# FEU-102-1_part5.net
KiCad netlist of a schematic drawn in Altium Designer
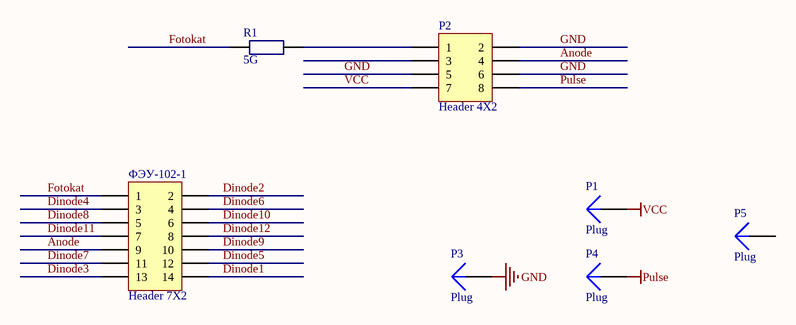
[diagram p0: FEU-102-1_part5.SchDoc]

(export (version "E")
  (design (tool "Eeschema 10.0.6"))
  (components
    (comp (ref "P1")
      (value "Plug")
      (footprint "PIN1")
      (fields (field (name "PUBLISHER") "Altium Limited"))
      (libsource (lib "Miscellaneous Connectors") (part "Plug"))
    )
    (comp (ref "P2")
      (value "Header 4X2")
      (footprint "HDR2X4")
      (description "Header, 4-Pin, Dual row")
      (fields (field (name "PUBLISHER") "Altium Limited"))
      (libsource (lib "Miscellaneous Connectors") (part "Header 4X2"))
    )
    (comp (ref "P3")
      (value "Plug")
      (footprint "PIN1")
      (fields (field (name "PUBLISHER") "Altium Limited"))
      (libsource (lib "Miscellaneous Connectors") (part "Plug"))
    )
    (comp (ref "P4")
      (value "Plug")
      (footprint "PIN1")
      (fields (field (name "PUBLISHER") "Altium Limited"))
      (libsource (lib "Miscellaneous Connectors") (part "Plug"))
    )
    (comp (ref "P5")
      (value "Plug")
      (footprint "PIN1")
      (fields (field (name "PUBLISHER") "Altium Limited"))
      (libsource (lib "Miscellaneous Connectors") (part "Plug"))
    )
    (comp (ref "R1")
      (value "5G")
      (footprint "HVF2512T5007FE")
      (libsource (lib "Микрон-3") (part "Resistor 0805"))
    )
    (comp (ref "ФЭУ-102-1")
      (value "Header 7X2")
      (footprint "ФЭУ-102")
      (description "Header, 7-Pin, Dual row")
      (fields (field (name "PUBLISHER") "Altium Limited"))
      (libsource (lib "Miscellaneous Connectors") (part "Header 7X2"))
    )
  )
  (nets
    (net (code "1") (name "/Anode") (class "Default")
      (node (ref "P2") (pin "4") (pinfunction "4_4") (pintype "passive"))
      (node (ref "ФЭУ-102-1") (pin "9") (pinfunction "9_9") (pintype "passive"))
    )
    (net (code "2") (name "/Dinode1") (class "Default")
      (node (ref "ФЭУ-102-1") (pin "14") (pinfunction "14_14") (pintype "passive"))
    )
    (net (code "3") (name "/Dinode2") (class "Default")
      (node (ref "ФЭУ-102-1") (pin "2") (pinfunction "2_2") (pintype "passive"))
    )
    (net (code "4") (name "/Dinode3") (class "Default")
      (node (ref "ФЭУ-102-1") (pin "13") (pinfunction "13_13") (pintype "passive"))
    )
    (net (code "5") (name "/Dinode4") (class "Default")
      (node (ref "ФЭУ-102-1") (pin "3") (pinfunction "3_3") (pintype "passive"))
    )
    (net (code "6") (name "/Dinode5") (class "Default")
      (node (ref "ФЭУ-102-1") (pin "12") (pinfunction "12_12") (pintype "passive"))
    )
    (net (code "7") (name "/Dinode6") (class "Default")
      (node (ref "ФЭУ-102-1") (pin "4") (pinfunction "4_4") (pintype "passive"))
    )
    (net (code "8") (name "/Dinode7") (class "Default")
      (node (ref "ФЭУ-102-1") (pin "11") (pinfunction "11_11") (pintype "passive"))
    )
    (net (code "9") (name "/Dinode8") (class "Default")
      (node (ref "ФЭУ-102-1") (pin "5") (pinfunction "5_5") (pintype "passive"))
    )
    (net (code "10") (name "/Dinode9") (class "Default")
      (node (ref "ФЭУ-102-1") (pin "10") (pinfunction "10_10") (pintype "passive"))
    )
    (net (code "11") (name "/Dinode10") (class "Default")
      (node (ref "ФЭУ-102-1") (pin "6") (pinfunction "6_6") (pintype "passive"))
    )
    (net (code "12") (name "/Dinode11") (class "Default")
      (node (ref "ФЭУ-102-1") (pin "7") (pinfunction "7_7") (pintype "passive"))
    )
    (net (code "13") (name "/Dinode12") (class "Default")
      (node (ref "ФЭУ-102-1") (pin "8") (pinfunction "8_8") (pintype "passive"))
    )
    (net (code "14") (name "/Fotokat") (class "Default")
      (node (ref "R1") (pin "1") (pinfunction "A_1") (pintype "passive"))
      (node (ref "ФЭУ-102-1") (pin "1") (pinfunction "1_1") (pintype "passive"))
    )
    (net (code "15") (name "GND") (class "Default")
      (node (ref "P2") (pin "2") (pinfunction "2_2") (pintype "passive"))
      (node (ref "P2") (pin "5") (pinfunction "5_5") (pintype "passive"))
      (node (ref "P2") (pin "6") (pinfunction "6_6") (pintype "passive"))
      (node (ref "P3") (pin "1") (pinfunction "1_1") (pintype "passive"))
    )
    (net (code "16") (name "Net-(P2-Pad1)") (class "Default")
      (node (ref "P2") (pin "1") (pinfunction "1_1") (pintype "passive"))
      (node (ref "R1") (pin "2") (pinfunction "2_2") (pintype "passive"))
    )
    (net (code "17") (name "Pulse") (class "Default")
      (node (ref "P2") (pin "8") (pinfunction "8_8") (pintype "passive"))
      (node (ref "P4") (pin "1") (pinfunction "1_1") (pintype "passive"))
    )
    (net (code "18") (name "VCC") (class "Default")
      (node (ref "P1") (pin "1") (pinfunction "1_1") (pintype "passive"))
      (node (ref "P2") (pin "7") (pinfunction "7_7") (pintype "passive"))
    )
    (net (code "19") (name "unconnected-(P2-Pad3)") (class "Default")
      (node (ref "P2") (pin "3") (pinfunction "3_3") (pintype "passive"))
    )
    (net (code "20") (name "unconnected-(P5-Pad1)") (class "Default")
      (node (ref "P5") (pin "1") (pinfunction "1_1") (pintype "passive"))
    )
  )
)
